# PWR_RAIL.net
KiCad netlist of a schematic drawn in Altium Designer
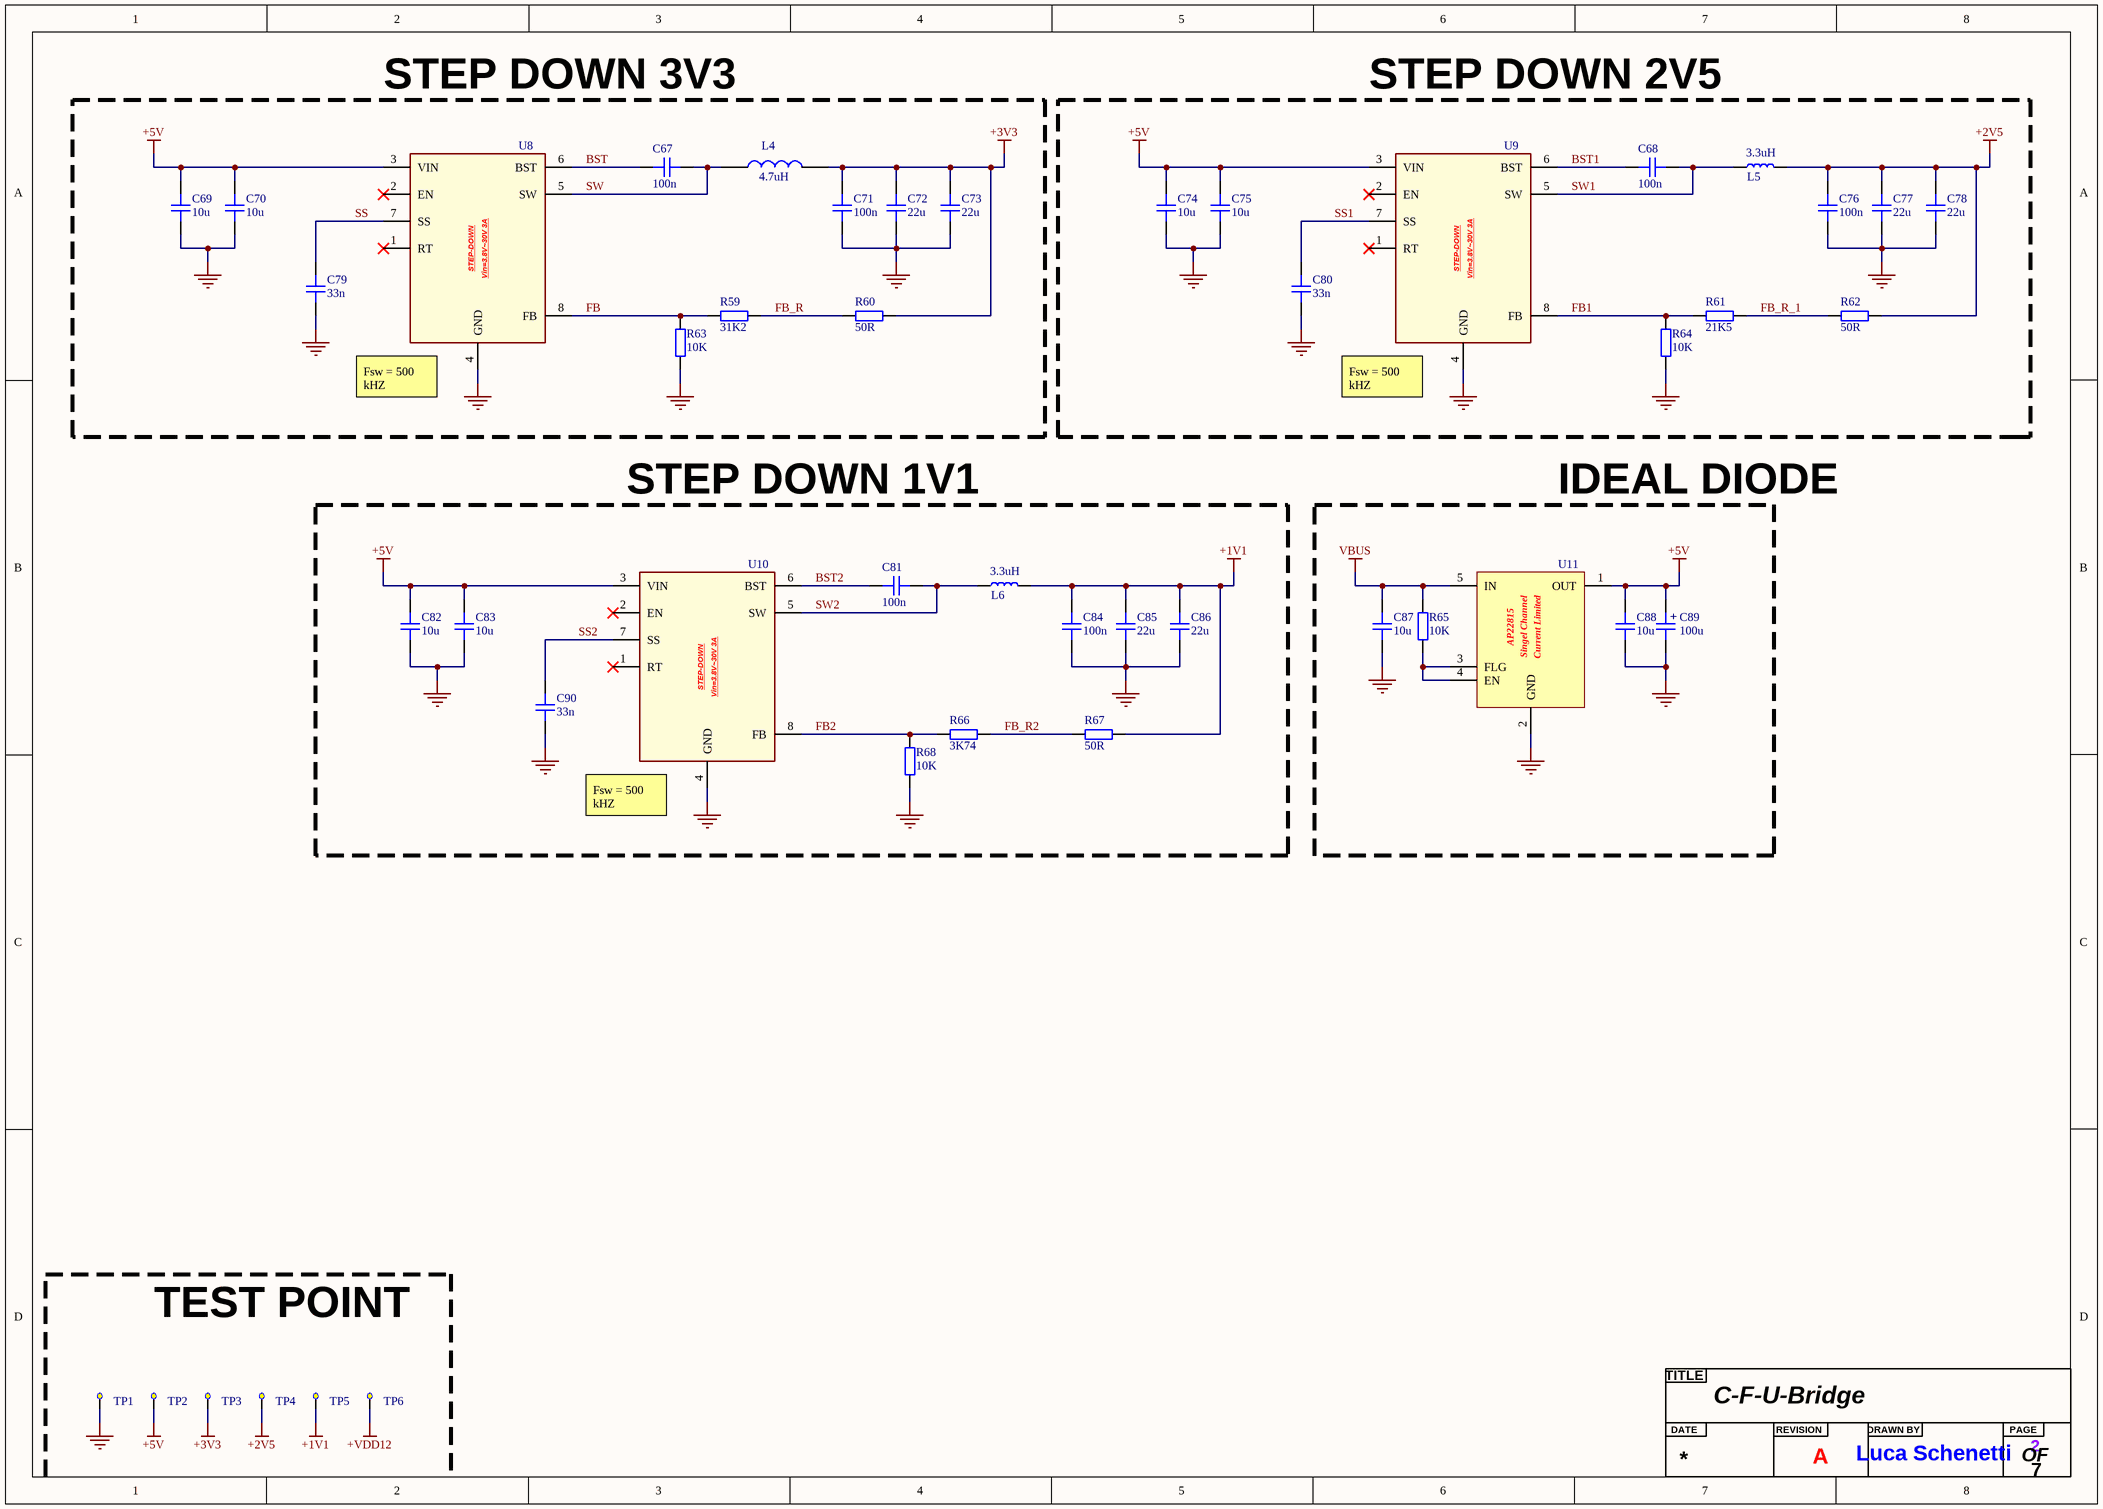
[diagram p0: PWR RAIL.SchDoc]

(export (version "E")
  (design (tool "Eeschema 10.0.6"))
  (components
    (comp (ref "C67")
      (value "100n")
      (footprint "CAP_0603")
      (description "Capacitor SMD 0603 [C14663]")
      (libsource (lib "Schematic-Lib-PhilsLab") (part "CAP_0603"))
    )
    (comp (ref "C68")
      (value "100n")
      (footprint "CAP_0603")
      (description "Capacitor SMD 0603 [C14663]")
      (libsource (lib "Schematic-Lib-PhilsLab") (part "CAP_0603"))
    )
    (comp (ref "C69")
      (value "10u")
      (footprint "CAP_0805")
      (description "Capacitor SMD 0805[C440198]")
      (libsource (lib "Schematic-Lib-PhilsLab") (part "CAP_0805"))
    )
    (comp (ref "C70")
      (value "10u")
      (footprint "CAP_0805")
      (description "Capacitor SMD 0805[C440198]")
      (libsource (lib "Schematic-Lib-PhilsLab") (part "CAP_0805"))
    )
    (comp (ref "C71")
      (value "100n")
      (footprint "CAP_0603")
      (description "Capacitor SMD 0603 [C14663]")
      (libsource (lib "Schematic-Lib-PhilsLab") (part "CAP_0603"))
    )
    (comp (ref "C72")
      (value "22u")
      (footprint "CAP_0603")
      (description "Capacitor SMD 0603 [C59461]")
      (libsource (lib "Schematic-Lib-PhilsLab") (part "CAP_0603"))
    )
    (comp (ref "C73")
      (value "22u")
      (footprint "CAP_0603")
      (description "Capacitor SMD 0603 [C59461]")
      (libsource (lib "Schematic-Lib-PhilsLab") (part "CAP_0603"))
    )
    (comp (ref "C74")
      (value "10u")
      (footprint "CAP_0805")
      (description "Capacitor SMD 0805[C440198]")
      (libsource (lib "Schematic-Lib-PhilsLab") (part "CAP_0805"))
    )
    (comp (ref "C75")
      (value "10u")
      (footprint "CAP_0805")
      (description "Capacitor SMD 0805[C440198]")
      (libsource (lib "Schematic-Lib-PhilsLab") (part "CAP_0805"))
    )
    (comp (ref "C76")
      (value "100n")
      (footprint "CAP_0603")
      (description "Capacitor SMD 0603 [C14663]")
      (libsource (lib "Schematic-Lib-PhilsLab") (part "CAP_0603"))
    )
    (comp (ref "C77")
      (value "22u")
      (footprint "CAP_0603")
      (description "Capacitor SMD 0603 [C59461]")
      (libsource (lib "Schematic-Lib-PhilsLab") (part "CAP_0603"))
    )
    (comp (ref "C78")
      (value "22u")
      (footprint "CAP_0603")
      (description "Capacitor SMD 0603 [C59461]")
      (libsource (lib "Schematic-Lib-PhilsLab") (part "CAP_0603"))
    )
    (comp (ref "C79")
      (value "33n")
      (footprint "CAP_0603")
      (description "[C21117]")
      (libsource (lib "Schematic-Lib-PhilsLab") (part "CAP_0603"))
    )
    (comp (ref "C80")
      (value "33n")
      (footprint "CAP_0603")
      (description "[C21117]")
      (libsource (lib "Schematic-Lib-PhilsLab") (part "CAP_0603"))
    )
    (comp (ref "C81")
      (value "100n")
      (footprint "CAP_0603")
      (description "Capacitor SMD 0603 [C14663]")
      (libsource (lib "Schematic-Lib-PhilsLab") (part "CAP_0603"))
    )
    (comp (ref "C82")
      (value "10u")
      (footprint "CAP_0805")
      (description "Capacitor SMD 0805[C440198]")
      (libsource (lib "Schematic-Lib-PhilsLab") (part "CAP_0805"))
    )
    (comp (ref "C83")
      (value "10u")
      (footprint "CAP_0805")
      (description "Capacitor SMD 0805[C440198]")
      (libsource (lib "Schematic-Lib-PhilsLab") (part "CAP_0805"))
    )
    (comp (ref "C84")
      (value "100n")
      (footprint "CAP_0603")
      (description "Capacitor SMD 0603 [C14663]")
      (libsource (lib "Schematic-Lib-PhilsLab") (part "CAP_0603"))
    )
    (comp (ref "C85")
      (value "22u")
      (footprint "CAP_0603")
      (description "Capacitor SMD 0603 [C59461]")
      (libsource (lib "Schematic-Lib-PhilsLab") (part "CAP_0603"))
    )
    (comp (ref "C86")
      (value "22u")
      (footprint "CAP_0603")
      (description "Capacitor SMD 0603 [C59461]")
      (libsource (lib "Schematic-Lib-PhilsLab") (part "CAP_0603"))
    )
    (comp (ref "C87")
      (value "10u")
      (footprint "CAP_0603")
      (description "[C96446]")
      (libsource (lib "Schematic-Lib-PhilsLab") (part "CAP_0603"))
    )
    (comp (ref "C88")
      (value "10u")
      (footprint "CAP_0603")
      (description "[C96446]")
      (libsource (lib "Schematic-Lib-PhilsLab") (part "CAP_0603"))
    )
    (comp (ref "C89")
      (value "100u")
      (footprint "CAP_AE_SMD_D6MM3_H5M55")
      (description "[C59936]")
      (libsource (lib "Schematic-Lib-PhilsLab") (part "CAP_ALEL_6.3x5.5"))
    )
    (comp (ref "C90")
      (value "33n")
      (footprint "CAP_0603")
      (description "[C21117]")
      (libsource (lib "Schematic-Lib-PhilsLab") (part "CAP_0603"))
    )
    (comp (ref "L4")
      (value "4.7uH")
      (footprint "FXL0530-4R7-M")
      (description "[C177246]")
      (libsource (lib "My_Library") (part "FXL0530-4R7-M"))
    )
    (comp (ref "L5")
      (value "3.3uH")
      (footprint "FXL0420-3R3-M")
      (description "[C167207]")
      (libsource (lib "My_Library") (part "FXL0420-3R3-M"))
    )
    (comp (ref "L6")
      (value "3.3uH")
      (footprint "FXL0420-3R3-M")
      (description "[C167207]")
      (libsource (lib "My_Library") (part "FXL0420-3R3-M"))
    )
    (comp (ref "R59")
      (value "31K2")
      (footprint "RES_0603")
      (description "[C863036]")
      (libsource (lib "Schematic-Lib-PhilsLab") (part "RES_0603"))
    )
    (comp (ref "R60")
      (value "50R")
      (footprint "RES_0603")
      (description "[C849792]")
      (libsource (lib "Schematic-Lib-PhilsLab") (part "RES_0603"))
    )
    (comp (ref "R61")
      (value "21K5")
      (footprint "RES_0603")
      (description "[C22911]")
      (libsource (lib "Schematic-Lib-PhilsLab") (part "RES_0603"))
    )
    (comp (ref "R62")
      (value "50R")
      (footprint "RES_0603")
      (description "[C849792]")
      (libsource (lib "Schematic-Lib-PhilsLab") (part "RES_0603"))
    )
    (comp (ref "R63")
      (value "10K")
      (footprint "RES_0603")
      (description "[C25804]")
      (libsource (lib "Schematic-Lib-PhilsLab") (part "RES_0603"))
    )
    (comp (ref "R64")
      (value "10K")
      (footprint "RES_0603")
      (description "[C25804]")
      (libsource (lib "Schematic-Lib-PhilsLab") (part "RES_0603"))
    )
    (comp (ref "R65")
      (value "10K")
      (footprint "RES_0603")
      (description "[C25804]")
      (libsource (lib "Schematic-Lib-PhilsLab") (part "RES_0603"))
    )
    (comp (ref "R66")
      (value "3K74")
      (footprint "RES_0603")
      (description "[C23016]")
      (libsource (lib "Schematic-Lib-PhilsLab") (part "RES_0603"))
    )
    (comp (ref "R67")
      (value "50R")
      (footprint "RES_0603")
      (description "[C849792]")
      (libsource (lib "Schematic-Lib-PhilsLab") (part "RES_0603"))
    )
    (comp (ref "R68")
      (value "10K")
      (footprint "RES_0603")
      (description "[C25804]")
      (libsource (lib "Schematic-Lib-PhilsLab") (part "RES_0603"))
    )
    (comp (ref "TP1")
      (value "Test Point")
      (footprint "Test Point")
      (libsource (lib "My_Library") (part "Test Point"))
    )
    (comp (ref "TP2")
      (value "Test Point")
      (footprint "Test Point")
      (libsource (lib "My_Library") (part "Test Point"))
    )
    (comp (ref "TP3")
      (value "Test Point")
      (footprint "Test Point")
      (libsource (lib "My_Library") (part "Test Point"))
    )
    (comp (ref "TP4")
      (value "Test Point")
      (footprint "Test Point")
      (libsource (lib "My_Library") (part "Test Point"))
    )
    (comp (ref "TP5")
      (value "Test Point")
      (footprint "Test Point")
      (libsource (lib "My_Library") (part "Test Point"))
    )
    (comp (ref "TP6")
      (value "Test Point")
      (footprint "Test Point")
      (libsource (lib "My_Library") (part "Test Point"))
    )
    (comp (ref "U8")
      (value "Step Down Converter 3A 3.8V~30V")
      (footprint "TPS62933DRLR")
      (description "[C3200405]")
      (libsource (lib "My_Library") (part "TPS62933DRLR"))
    )
    (comp (ref "U9")
      (value "Step Down Converter 3A 3.8V~30V")
      (footprint "TPS62933DRLR")
      (description "[C3200405]")
      (libsource (lib "My_Library") (part "TPS62933DRLR"))
    )
    (comp (ref "U10")
      (value "Step Down Converter 3A 3.8V~30V")
      (footprint "TPS62933DRLR")
      (description "[C3200405]")
      (libsource (lib "My_Library") (part "TPS62933DRLR"))
    )
    (comp (ref "U11")
      (value "Single-Channel, Current-Limited")
      (footprint "AP22815")
      (description "[C2150007]")
      (libsource (lib "My_Library") (part "AP22815AWT-7"))
    )
  )
  (nets
    (net (code "1") (name "+1V1") (class "Default")
      (node (ref "C84") (pin "1") (pinfunction "1_1") (pintype "passive"))
      (node (ref "C85") (pin "2") (pinfunction "2_2") (pintype "passive"))
      (node (ref "C86") (pin "2") (pinfunction "2_2") (pintype "passive"))
      (node (ref "L6") (pin "2") (pinfunction "2_2") (pintype "passive"))
      (node (ref "R67") (pin "1") (pinfunction "1_1") (pintype "passive"))
      (node (ref "TP5") (pin "1") (pinfunction "Test_Point_1") (pintype "passive"))
    )
    (net (code "2") (name "+2V5") (class "Default")
      (node (ref "C76") (pin "1") (pinfunction "1_1") (pintype "passive"))
      (node (ref "C77") (pin "2") (pinfunction "2_2") (pintype "passive"))
      (node (ref "C78") (pin "2") (pinfunction "2_2") (pintype "passive"))
      (node (ref "L5") (pin "2") (pinfunction "2_2") (pintype "passive"))
      (node (ref "R62") (pin "1") (pinfunction "1_1") (pintype "passive"))
      (node (ref "TP4") (pin "1") (pinfunction "Test_Point_1") (pintype "passive"))
    )
    (net (code "3") (name "+3V3") (class "Default")
      (node (ref "C71") (pin "1") (pinfunction "1_1") (pintype "passive"))
      (node (ref "C72") (pin "2") (pinfunction "2_2") (pintype "passive"))
      (node (ref "C73") (pin "2") (pinfunction "2_2") (pintype "passive"))
      (node (ref "L4") (pin "2") (pinfunction "2_2") (pintype "passive"))
      (node (ref "R60") (pin "1") (pinfunction "1_1") (pintype "passive"))
      (node (ref "TP3") (pin "1") (pinfunction "Test_Point_1") (pintype "passive"))
    )
    (net (code "4") (name "+5V") (class "Default")
      (node (ref "C69") (pin "2") (pinfunction "2_2") (pintype "passive"))
      (node (ref "C70") (pin "2") (pinfunction "2_2") (pintype "passive"))
      (node (ref "C74") (pin "2") (pinfunction "2_2") (pintype "passive"))
      (node (ref "C75") (pin "2") (pinfunction "2_2") (pintype "passive"))
      (node (ref "C82") (pin "2") (pinfunction "2_2") (pintype "passive"))
      (node (ref "C83") (pin "2") (pinfunction "2_2") (pintype "passive"))
      (node (ref "C88") (pin "2") (pinfunction "2_2") (pintype "passive"))
      (node (ref "C89") (pin "1") (pinfunction "1_1") (pintype "passive"))
      (node (ref "TP2") (pin "1") (pinfunction "Test_Point_1") (pintype "passive"))
      (node (ref "U10") (pin "3") (pinfunction "VIN_3") (pintype "passive"))
      (node (ref "U11") (pin "1") (pinfunction "OUT_1") (pintype "passive"))
      (node (ref "U8") (pin "3") (pinfunction "VIN_3") (pintype "passive"))
      (node (ref "U9") (pin "3") (pinfunction "VIN_3") (pintype "passive"))
    )
    (net (code "5") (name "+VDD12") (class "Default")
      (node (ref "TP6") (pin "1") (pinfunction "Test_Point_1") (pintype "passive"))
    )
    (net (code "6") (name "/BST") (class "Default")
      (node (ref "C67") (pin "2") (pinfunction "2_2") (pintype "passive"))
      (node (ref "U8") (pin "6") (pinfunction "BST_6") (pintype "passive"))
    )
    (net (code "7") (name "/BST1") (class "Default")
      (node (ref "C68") (pin "2") (pinfunction "2_2") (pintype "passive"))
      (node (ref "U9") (pin "6") (pinfunction "BST_6") (pintype "passive"))
    )
    (net (code "8") (name "/BST2") (class "Default")
      (node (ref "C81") (pin "2") (pinfunction "2_2") (pintype "passive"))
      (node (ref "U10") (pin "6") (pinfunction "BST_6") (pintype "passive"))
    )
    (net (code "9") (name "/FB") (class "Default")
      (node (ref "R59") (pin "2") (pinfunction "2_2") (pintype "passive"))
      (node (ref "R63") (pin "2") (pinfunction "2_2") (pintype "passive"))
      (node (ref "U8") (pin "8") (pinfunction "FB_8") (pintype "passive"))
    )
    (net (code "10") (name "/FB1") (class "Default")
      (node (ref "R61") (pin "2") (pinfunction "2_2") (pintype "passive"))
      (node (ref "R64") (pin "2") (pinfunction "2_2") (pintype "passive"))
      (node (ref "U9") (pin "8") (pinfunction "FB_8") (pintype "passive"))
    )
    (net (code "11") (name "/FB2") (class "Default")
      (node (ref "R66") (pin "2") (pinfunction "2_2") (pintype "passive"))
      (node (ref "R68") (pin "2") (pinfunction "2_2") (pintype "passive"))
      (node (ref "U10") (pin "8") (pinfunction "FB_8") (pintype "passive"))
    )
    (net (code "12") (name "/FB_R") (class "Default")
      (node (ref "R59") (pin "1") (pinfunction "1_1") (pintype "passive"))
      (node (ref "R60") (pin "2") (pinfunction "2_2") (pintype "passive"))
    )
    (net (code "13") (name "/FB_R2") (class "Default")
      (node (ref "R66") (pin "1") (pinfunction "1_1") (pintype "passive"))
      (node (ref "R67") (pin "2") (pinfunction "2_2") (pintype "passive"))
    )
    (net (code "14") (name "/FB_R_1") (class "Default")
      (node (ref "R61") (pin "1") (pinfunction "1_1") (pintype "passive"))
      (node (ref "R62") (pin "2") (pinfunction "2_2") (pintype "passive"))
    )
    (net (code "15") (name "/SS") (class "Default")
      (node (ref "C79") (pin "1") (pinfunction "1_1") (pintype "passive"))
      (node (ref "U8") (pin "7") (pinfunction "SS_7") (pintype "passive"))
    )
    (net (code "16") (name "/SS1") (class "Default")
      (node (ref "C80") (pin "1") (pinfunction "1_1") (pintype "passive"))
      (node (ref "U9") (pin "7") (pinfunction "SS_7") (pintype "passive"))
    )
    (net (code "17") (name "/SS2") (class "Default")
      (node (ref "C90") (pin "1") (pinfunction "1_1") (pintype "passive"))
      (node (ref "U10") (pin "7") (pinfunction "SS_7") (pintype "passive"))
    )
    (net (code "18") (name "/SW") (class "Default")
      (node (ref "C67") (pin "1") (pinfunction "1_1") (pintype "passive"))
      (node (ref "L4") (pin "1") (pinfunction "1_1") (pintype "passive"))
      (node (ref "U8") (pin "5") (pinfunction "SW_5") (pintype "passive"))
    )
    (net (code "19") (name "/SW1") (class "Default")
      (node (ref "C68") (pin "1") (pinfunction "1_1") (pintype "passive"))
      (node (ref "L5") (pin "1") (pinfunction "1_1") (pintype "passive"))
      (node (ref "U9") (pin "5") (pinfunction "SW_5") (pintype "passive"))
    )
    (net (code "20") (name "/SW2") (class "Default")
      (node (ref "C81") (pin "1") (pinfunction "1_1") (pintype "passive"))
      (node (ref "L6") (pin "1") (pinfunction "1_1") (pintype "passive"))
      (node (ref "U10") (pin "5") (pinfunction "SW_5") (pintype "passive"))
    )
    (net (code "21") (name "GND") (class "Default")
      (node (ref "C69") (pin "1") (pinfunction "1_1") (pintype "passive"))
      (node (ref "C70") (pin "1") (pinfunction "1_1") (pintype "passive"))
      (node (ref "C71") (pin "2") (pinfunction "2_2") (pintype "passive"))
      (node (ref "C72") (pin "1") (pinfunction "1_1") (pintype "passive"))
      (node (ref "C73") (pin "1") (pinfunction "1_1") (pintype "passive"))
      (node (ref "C74") (pin "1") (pinfunction "1_1") (pintype "passive"))
      (node (ref "C75") (pin "1") (pinfunction "1_1") (pintype "passive"))
      (node (ref "C76") (pin "2") (pinfunction "2_2") (pintype "passive"))
      (node (ref "C77") (pin "1") (pinfunction "1_1") (pintype "passive"))
      (node (ref "C78") (pin "1") (pinfunction "1_1") (pintype "passive"))
      (node (ref "C79") (pin "2") (pinfunction "2_2") (pintype "passive"))
      (node (ref "C80") (pin "2") (pinfunction "2_2") (pintype "passive"))
      (node (ref "C82") (pin "1") (pinfunction "1_1") (pintype "passive"))
      (node (ref "C83") (pin "1") (pinfunction "1_1") (pintype "passive"))
      (node (ref "C84") (pin "2") (pinfunction "2_2") (pintype "passive"))
      (node (ref "C85") (pin "1") (pinfunction "1_1") (pintype "passive"))
      (node (ref "C86") (pin "1") (pinfunction "1_1") (pintype "passive"))
      (node (ref "C87") (pin "1") (pinfunction "1_1") (pintype "passive"))
      (node (ref "C88") (pin "1") (pinfunction "1_1") (pintype "passive"))
      (node (ref "C89") (pin "2") (pinfunction "2_2") (pintype "passive"))
      (node (ref "C90") (pin "2") (pinfunction "2_2") (pintype "passive"))
      (node (ref "R63") (pin "1") (pinfunction "1_1") (pintype "passive"))
      (node (ref "R64") (pin "1") (pinfunction "1_1") (pintype "passive"))
      (node (ref "R68") (pin "1") (pinfunction "1_1") (pintype "passive"))
      (node (ref "TP1") (pin "1") (pinfunction "Test_Point_1") (pintype "passive"))
      (node (ref "U10") (pin "4") (pinfunction "GND_4") (pintype "power_in"))
      (node (ref "U11") (pin "2") (pinfunction "GND_2") (pintype "passive"))
      (node (ref "U8") (pin "4") (pinfunction "GND_4") (pintype "power_in"))
      (node (ref "U9") (pin "4") (pinfunction "GND_4") (pintype "power_in"))
    )
    (net (code "22") (name "Net-(U11-EN)") (class "Default")
      (node (ref "R65") (pin "1") (pinfunction "1_1") (pintype "passive"))
      (node (ref "U11") (pin "3") (pinfunction "FLG_3") (pintype "passive"))
      (node (ref "U11") (pin "4") (pinfunction "EN_4") (pintype "passive"))
    )
    (net (code "23") (name "VBUS") (class "Default")
      (node (ref "C87") (pin "2") (pinfunction "2_2") (pintype "passive"))
      (node (ref "R65") (pin "2") (pinfunction "2_2") (pintype "passive"))
      (node (ref "U11") (pin "5") (pinfunction "IN_5") (pintype "passive"))
    )
    (net (code "24") (name "unconnected-(U8-EN-Pad2)") (class "Default")
      (node (ref "U8") (pin "2") (pinfunction "EN_2") (pintype "passive+no_connect"))
    )
    (net (code "25") (name "unconnected-(U8-RT-Pad1)") (class "Default")
      (node (ref "U8") (pin "1") (pinfunction "RT_1") (pintype "passive+no_connect"))
    )
    (net (code "26") (name "unconnected-(U9-EN-Pad2)") (class "Default")
      (node (ref "U9") (pin "2") (pinfunction "EN_2") (pintype "passive+no_connect"))
    )
    (net (code "27") (name "unconnected-(U9-RT-Pad1)") (class "Default")
      (node (ref "U9") (pin "1") (pinfunction "RT_1") (pintype "passive+no_connect"))
    )
    (net (code "28") (name "unconnected-(U10-EN-Pad2)") (class "Default")
      (node (ref "U10") (pin "2") (pinfunction "EN_2") (pintype "passive+no_connect"))
    )
    (net (code "29") (name "unconnected-(U10-RT-Pad1)") (class "Default")
      (node (ref "U10") (pin "1") (pinfunction "RT_1") (pintype "passive+no_connect"))
    )
  )
)
